# Control_Board_v0_1.net
KiCad netlist of a schematic drawn in EAGLE
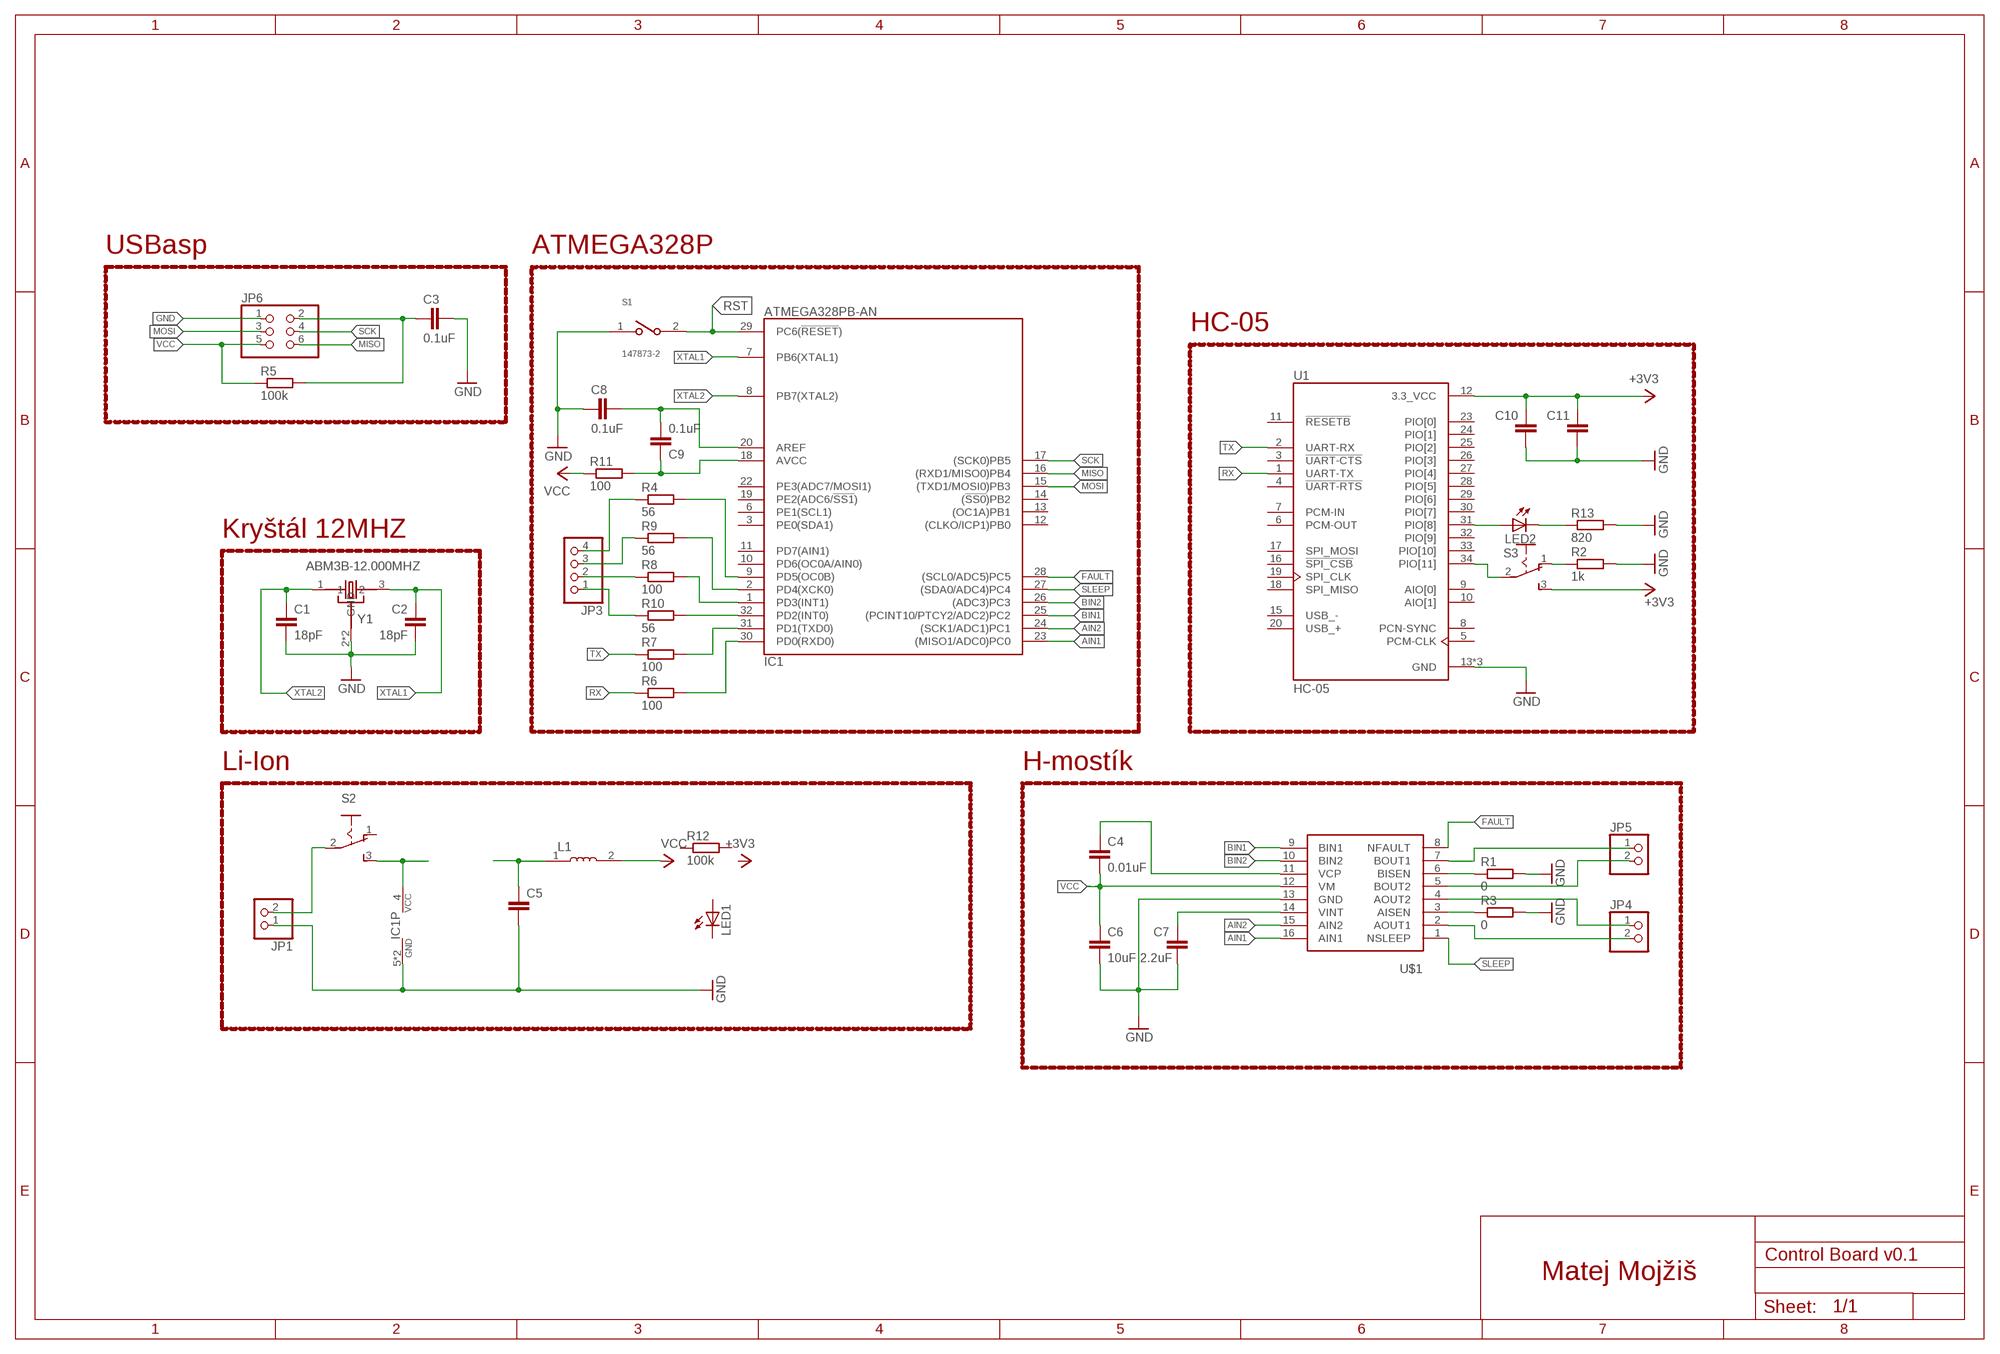
[diagram p0: schematic, sheet 1]

(export (version "E")
  (design (tool "Eeschema 10.0.6"))
  (components
    (comp (ref "C1")
      (value "18pF")
      (footprint "eagle-import:C0805")
      (libsource (lib "eagle-import") (part "C-EUC0805"))
    )
    (comp (ref "C2")
      (value "18pF")
      (footprint "eagle-import:C0805")
      (libsource (lib "eagle-import") (part "C-EUC0805"))
    )
    (comp (ref "C3")
      (value "0.1uF")
      (footprint "eagle-import:C0805")
      (libsource (lib "eagle-import") (part "C-EUC0805"))
    )
    (comp (ref "C4")
      (value "0.01uF")
      (footprint "eagle-import:C0805")
      (libsource (lib "eagle-import") (part "C-EUC0805"))
    )
    (comp (ref "C5")
      (value "C-EUC0805")
      (footprint "eagle-import:C0805")
      (libsource (lib "eagle-import") (part "C-EUC0805"))
    )
    (comp (ref "C6")
      (value "10uF")
      (footprint "eagle-import:C0805")
      (libsource (lib "eagle-import") (part "C-EUC0805"))
    )
    (comp (ref "C7")
      (value "2.2uF")
      (footprint "eagle-import:C0805")
      (libsource (lib "eagle-import") (part "C-EUC0805"))
    )
    (comp (ref "C8")
      (value "0.1uF")
      (footprint "eagle-import:C0805")
      (libsource (lib "eagle-import") (part "C-EUC0805"))
    )
    (comp (ref "C9")
      (value "0.1uF")
      (footprint "eagle-import:C0805")
      (libsource (lib "eagle-import") (part "C-EUC0805"))
    )
    (comp (ref "C10")
      (value "C-EUC0805")
      (footprint "eagle-import:C0805")
      (libsource (lib "eagle-import") (part "C-EUC0805"))
    )
    (comp (ref "C11")
      (value "C-EUC0805")
      (footprint "eagle-import:C0805")
      (libsource (lib "eagle-import") (part "C-EUC0805"))
    )
    (comp (ref "IC1")
      (value "ATMEGA328PB-AN")
      (footprint "eagle-import:QFP32_7X7_0.80")
      (libsource (lib "eagle-import") (part "ATMEGA328PB-AN"))
    )
    (comp (ref "JP1")
      (value "PINHD-1X2/90")
      (footprint "eagle-import:1X02_90")
      (libsource (lib "eagle-import") (part "PINHD-1X2/90"))
    )
    (comp (ref "JP3")
      (value "PINHD-1X4")
      (footprint "eagle-import:1X04")
      (libsource (lib "eagle-import") (part "PINHD-1X4"))
    )
    (comp (ref "JP4")
      (value "PINHD-1X2/90")
      (footprint "eagle-import:1X02_90")
      (libsource (lib "eagle-import") (part "PINHD-1X2/90"))
    )
    (comp (ref "JP5")
      (value "PINHD-1X2/90")
      (footprint "eagle-import:1X02_90")
      (libsource (lib "eagle-import") (part "PINHD-1X2/90"))
    )
    (comp (ref "JP6")
      (value "PINHD-2X3")
      (footprint "eagle-import:2X03")
      (libsource (lib "eagle-import") (part "PINHD-2X3"))
    )
    (comp (ref "L1")
      (value "MLF2012C330KT000")
      (footprint "eagle-import:INDC2012X87N")
      (fields (field (name "MF") "TDK"))
      (libsource (lib "eagle-import") (part "MLF2012C330KT000"))
    )
    (comp (ref "LED1")
      (value "LEDCHIPLED_0805")
      (footprint "eagle-import:CHIPLED_0805")
      (libsource (lib "eagle-import") (part "LEDCHIPLED_0805"))
    )
    (comp (ref "LED2")
      (value "LEDCHIPLED_0805")
      (footprint "eagle-import:CHIPLED_0805")
      (libsource (lib "eagle-import") (part "LEDCHIPLED_0805"))
    )
    (comp (ref "R1")
      (value "0")
      (footprint "eagle-import:R0805")
      (libsource (lib "eagle-import") (part "R-EU_R0805"))
    )
    (comp (ref "R2")
      (value "1k")
      (footprint "eagle-import:R0805")
      (libsource (lib "eagle-import") (part "R-EU_R0805"))
    )
    (comp (ref "R3")
      (value "0")
      (footprint "eagle-import:R0805")
      (libsource (lib "eagle-import") (part "R-EU_R0805"))
    )
    (comp (ref "R4")
      (value "56")
      (footprint "eagle-import:R0805")
      (libsource (lib "eagle-import") (part "R-EU_R0805"))
    )
    (comp (ref "R5")
      (value "100k")
      (footprint "eagle-import:R0805")
      (libsource (lib "eagle-import") (part "R-EU_R0805"))
    )
    (comp (ref "R6")
      (value "100")
      (footprint "eagle-import:R0805")
      (libsource (lib "eagle-import") (part "R-EU_R0805"))
    )
    (comp (ref "R7")
      (value "100")
      (footprint "eagle-import:R0805")
      (libsource (lib "eagle-import") (part "R-EU_R0805"))
    )
    (comp (ref "R8")
      (value "100")
      (footprint "eagle-import:R0805")
      (libsource (lib "eagle-import") (part "R-EU_R0805"))
    )
    (comp (ref "R9")
      (value "56")
      (footprint "eagle-import:R0805")
      (libsource (lib "eagle-import") (part "R-EU_R0805"))
    )
    (comp (ref "R10")
      (value "56")
      (footprint "eagle-import:R0805")
      (libsource (lib "eagle-import") (part "R-EU_R0805"))
    )
    (comp (ref "R11")
      (value "100")
      (footprint "eagle-import:R0805")
      (libsource (lib "eagle-import") (part "R-EU_R0805"))
    )
    (comp (ref "R12")
      (value "100k")
      (footprint "eagle-import:R0805")
      (libsource (lib "eagle-import") (part "R-EU_R0805"))
    )
    (comp (ref "R13")
      (value "820")
      (footprint "eagle-import:R0805")
      (libsource (lib "eagle-import") (part "R-EU_R0805"))
    )
    (comp (ref "S1")
      (value "147873-2")
      (footprint "eagle-import:SW_147873-2")
      (fields (field (name "MF") "TE Connectivity"))
      (libsource (lib "eagle-import") (part "147873-2"))
    )
    (comp (ref "S2")
      (value "255SB")
      (footprint "eagle-import:255SB")
      (libsource (lib "eagle-import") (part "255SB"))
    )
    (comp (ref "S3")
      (value "M251")
      (footprint "eagle-import:M251")
      (libsource (lib "eagle-import") (part "M251"))
    )
    (comp (ref "U$1")
      (value "DVR8833SUPERFICIAL")
      (footprint "eagle-import:PWP16")
      (libsource (lib "eagle-import") (part "DVR8833SUPERFICIAL"))
    )
    (comp (ref "U1")
      (value "HC-05")
      (footprint "eagle-import:XCVR_HC-05")
      (fields (field (name "MF") "Bel Power solution"))
      (libsource (lib "eagle-import") (part "HC-05"))
    )
    (comp (ref "Y1")
      (value "ABM3B-12.000MHZ")
      (footprint "eagle-import:OSCSC500X320X110-4N")
      (fields (field (name "MF") "Abracon") (field (name "MP") "ABM3B-8.000MHZ-B2-T"))
      (libsource (lib "eagle-import") (part "ABM3B-8.000MHZ-B2-T"))
    )
  )
  (nets
    (net (code "1") (name "+3V3") (class "Default")
      (node (ref "C10") (pin "1") (pinfunction "1_1") (pintype "passive"))
      (node (ref "C11") (pin "1") (pinfunction "1_1") (pintype "passive"))
      (node (ref "S3") (pin "3") (pinfunction "S_3") (pintype "passive"))
      (node (ref "U1") (pin "12") (pinfunction "3.3_VCC_12") (pintype "power_in"))
    )
    (net (code "2") (name "AIN1") (class "Default")
      (node (ref "IC1") (pin "23") (pinfunction "(MISO1/ADC0)PC0_23") (pintype "bidirectional"))
      (node (ref "U$1") (pin "16") (pinfunction "AIN1_16") (pintype "bidirectional"))
    )
    (net (code "3") (name "AIN2") (class "Default")
      (node (ref "IC1") (pin "24") (pinfunction "(SCK1/ADC1)PC1_24") (pintype "bidirectional"))
      (node (ref "U$1") (pin "15") (pinfunction "AIN2_15") (pintype "bidirectional"))
    )
    (net (code "4") (name "BIN1") (class "Default")
      (node (ref "IC1") (pin "25") (pinfunction "(PCINT10/PTCY2/ADC2)PC2_25") (pintype "bidirectional"))
      (node (ref "U$1") (pin "9") (pinfunction "BIN1_9") (pintype "bidirectional"))
    )
    (net (code "5") (name "BIN2") (class "Default")
      (node (ref "IC1") (pin "26") (pinfunction "(ADC3)PC3_26") (pintype "bidirectional"))
      (node (ref "U$1") (pin "10") (pinfunction "BIN2_10") (pintype "bidirectional"))
    )
    (net (code "6") (name "FAULT") (class "Default")
      (node (ref "IC1") (pin "28") (pinfunction "(SCL0/ADC5)PC5_28") (pintype "bidirectional"))
      (node (ref "U$1") (pin "8") (pinfunction "NFAULT_8") (pintype "bidirectional"))
    )
    (net (code "7") (name "GND") (class "Default")
      (node (ref "C1") (pin "2") (pinfunction "2_2") (pintype "passive"))
      (node (ref "C10") (pin "2") (pinfunction "2_2") (pintype "passive"))
      (node (ref "C11") (pin "2") (pinfunction "2_2") (pintype "passive"))
      (node (ref "C2") (pin "2") (pinfunction "2_2") (pintype "passive"))
      (node (ref "C3") (pin "1") (pinfunction "1_1") (pintype "passive"))
      (node (ref "C5") (pin "2") (pinfunction "2_2") (pintype "passive"))
      (node (ref "C6") (pin "2") (pinfunction "2_2") (pintype "passive"))
      (node (ref "C7") (pin "2") (pinfunction "2_2") (pintype "passive"))
      (node (ref "C8") (pin "2") (pinfunction "2_2") (pintype "passive"))
      (node (ref "IC1") (pin "21") (pinfunction "GND_21") (pintype "power_in"))
      (node (ref "IC1") (pin "5") (pinfunction "GND_5") (pintype "power_in"))
      (node (ref "JP1") (pin "1") (pinfunction "1_1") (pintype "passive"))
      (node (ref "JP6") (pin "1") (pinfunction "1_1") (pintype "passive"))
      (node (ref "R1") (pin "2") (pinfunction "2_2") (pintype "passive"))
      (node (ref "R13") (pin "2") (pinfunction "2_2") (pintype "passive"))
      (node (ref "R2") (pin "2") (pinfunction "2_2") (pintype "passive"))
      (node (ref "R3") (pin "2") (pinfunction "2_2") (pintype "passive"))
      (node (ref "S1") (pin "1") (pinfunction "1_1") (pintype "passive"))
      (node (ref "U$1") (pin "13") (pinfunction "GND_13") (pintype "bidirectional"))
      (node (ref "U1") (pin "13") (pinfunction "GND_13") (pintype "power_in"))
      (node (ref "U1") (pin "21") (pinfunction "GND_21") (pintype "power_in"))
      (node (ref "U1") (pin "22") (pinfunction "GND_22") (pintype "power_in"))
      (node (ref "Y1") (pin "2") (pinfunction "GND_2") (pintype "passive"))
      (node (ref "Y1") (pin "4") (pinfunction "GND_4") (pintype "passive"))
    )
    (net (code "8") (name "MISO") (class "Default")
      (node (ref "IC1") (pin "16") (pinfunction "(RXD1/MISO0)PB4_16") (pintype "bidirectional"))
      (node (ref "JP6") (pin "6") (pinfunction "6_6") (pintype "passive"))
    )
    (net (code "9") (name "MOSI") (class "Default")
      (node (ref "IC1") (pin "15") (pinfunction "(TXD1/MOSI0)PB3_15") (pintype "bidirectional"))
      (node (ref "JP6") (pin "3") (pinfunction "3_3") (pintype "passive"))
    )
    (net (code "10") (name "Net-(C5-Pad1)") (class "Default")
      (node (ref "C5") (pin "1") (pinfunction "1_1") (pintype "passive"))
      (node (ref "L1") (pin "1") (pinfunction "1_1") (pintype "passive"))
    )
    (net (code "11") (name "Net-(IC1A-AREF)") (class "Default")
      (node (ref "C8") (pin "1") (pinfunction "1_1") (pintype "passive"))
      (node (ref "C9") (pin "2") (pinfunction "2_2") (pintype "passive"))
      (node (ref "IC1") (pin "20") (pinfunction "AREF_20") (pintype "passive"))
    )
    (net (code "12") (name "Net-(IC1A-AVCC)") (class "Default")
      (node (ref "C9") (pin "1") (pinfunction "1_1") (pintype "passive"))
      (node (ref "IC1") (pin "18") (pinfunction "AVCC_18") (pintype "power_in"))
      (node (ref "R11") (pin "2") (pinfunction "2_2") (pintype "passive"))
    )
    (net (code "13") (name "Net-(IC1A-PD0(RXD0))") (class "Default")
      (node (ref "IC1") (pin "30") (pinfunction "PD0(RXD0)_30") (pintype "bidirectional"))
      (node (ref "R6") (pin "2") (pinfunction "2_2") (pintype "passive"))
    )
    (net (code "14") (name "Net-(IC1A-PD1(TXD0))") (class "Default")
      (node (ref "IC1") (pin "31") (pinfunction "PD1(TXD0)_31") (pintype "bidirectional"))
      (node (ref "R7") (pin "2") (pinfunction "2_2") (pintype "passive"))
    )
    (net (code "15") (name "Net-(IC1A-PD2(INT0))") (class "Default")
      (node (ref "IC1") (pin "32") (pinfunction "PD2(INT0)_32") (pintype "bidirectional"))
      (node (ref "R10") (pin "2") (pinfunction "2_2") (pintype "passive"))
    )
    (net (code "16") (name "Net-(IC1A-PD3(INT1))") (class "Default")
      (node (ref "IC1") (pin "1") (pinfunction "PD3(INT1)_1") (pintype "bidirectional"))
      (node (ref "R8") (pin "2") (pinfunction "2_2") (pintype "passive"))
    )
    (net (code "17") (name "Net-(IC1A-PD4(XCK0))") (class "Default")
      (node (ref "IC1") (pin "2") (pinfunction "PD4(XCK0)_2") (pintype "bidirectional"))
      (node (ref "R9") (pin "2") (pinfunction "2_2") (pintype "passive"))
    )
    (net (code "18") (name "Net-(IC1A-PD5(OC0B))") (class "Default")
      (node (ref "IC1") (pin "9") (pinfunction "PD5(OC0B)_9") (pintype "bidirectional"))
      (node (ref "R4") (pin "2") (pinfunction "2_2") (pintype "passive"))
    )
    (net (code "19") (name "Net-(IC1B-VCC)") (class "Default")
      (node (ref "IC1") (pin "4") (pinfunction "VCC_4") (pintype "power_in"))
      (node (ref "S2") (pin "3") (pinfunction "S_3") (pintype "passive"))
    )
    (net (code "20") (name "Net-(JP3-Pad1)") (class "Default")
      (node (ref "JP3") (pin "1") (pinfunction "1_1") (pintype "passive"))
      (node (ref "R10") (pin "1") (pinfunction "1_1") (pintype "passive"))
    )
    (net (code "21") (name "Net-(JP3-Pad2)") (class "Default")
      (node (ref "JP3") (pin "2") (pinfunction "2_2") (pintype "passive"))
      (node (ref "R8") (pin "1") (pinfunction "1_1") (pintype "passive"))
    )
    (net (code "22") (name "Net-(JP3-Pad3)") (class "Default")
      (node (ref "JP3") (pin "3") (pinfunction "3_3") (pintype "passive"))
      (node (ref "R9") (pin "1") (pinfunction "1_1") (pintype "passive"))
    )
    (net (code "23") (name "Net-(JP3-Pad4)") (class "Default")
      (node (ref "JP3") (pin "4") (pinfunction "4_4") (pintype "passive"))
      (node (ref "R4") (pin "1") (pinfunction "1_1") (pintype "passive"))
    )
    (net (code "24") (name "Net-(LED2-PadC)") (class "Default")
      (node (ref "LED2") (pin "C") (pinfunction "C_C") (pintype "passive"))
      (node (ref "R13") (pin "1") (pinfunction "1_1") (pintype "passive"))
    )
    (net (code "25") (name "Net-(S2-P)") (class "Default")
      (node (ref "JP1") (pin "2") (pinfunction "2_2") (pintype "passive"))
      (node (ref "S2") (pin "2") (pinfunction "P_2") (pintype "passive"))
    )
    (net (code "26") (name "Net-(S3-O)") (class "Default")
      (node (ref "R2") (pin "1") (pinfunction "1_1") (pintype "passive"))
      (node (ref "S3") (pin "1") (pinfunction "O_1") (pintype "passive"))
    )
    (net (code "27") (name "Net-(S3-P)") (class "Default")
      (node (ref "S3") (pin "2") (pinfunction "P_2") (pintype "passive"))
      (node (ref "U1") (pin "34") (pinfunction "PIO[11]_34") (pintype "bidirectional"))
    )
    (net (code "28") (name "Net-(U$1-AISEN)") (class "Default")
      (node (ref "R3") (pin "1") (pinfunction "1_1") (pintype "passive"))
      (node (ref "U$1") (pin "3") (pinfunction "AISEN_3") (pintype "bidirectional"))
    )
    (net (code "29") (name "Net-(U$1-AOUT1)") (class "Default")
      (node (ref "JP4") (pin "2") (pinfunction "2_2") (pintype "passive"))
      (node (ref "U$1") (pin "2") (pinfunction "AOUT1_2") (pintype "bidirectional"))
    )
    (net (code "30") (name "Net-(U$1-AOUT2)") (class "Default")
      (node (ref "JP4") (pin "1") (pinfunction "1_1") (pintype "passive"))
      (node (ref "U$1") (pin "4") (pinfunction "AOUT2_4") (pintype "bidirectional"))
    )
    (net (code "31") (name "Net-(U$1-BISEN)") (class "Default")
      (node (ref "R1") (pin "1") (pinfunction "1_1") (pintype "passive"))
      (node (ref "U$1") (pin "6") (pinfunction "BISEN_6") (pintype "bidirectional"))
    )
    (net (code "32") (name "Net-(U$1-BOUT1)") (class "Default")
      (node (ref "JP5") (pin "1") (pinfunction "1_1") (pintype "passive"))
      (node (ref "U$1") (pin "7") (pinfunction "BOUT1_7") (pintype "bidirectional"))
    )
    (net (code "33") (name "Net-(U$1-BOUT2)") (class "Default")
      (node (ref "JP5") (pin "2") (pinfunction "2_2") (pintype "passive"))
      (node (ref "U$1") (pin "5") (pinfunction "BOUT2_5") (pintype "bidirectional"))
    )
    (net (code "34") (name "Net-(U$1-VCP)") (class "Default")
      (node (ref "C4") (pin "1") (pinfunction "1_1") (pintype "passive"))
      (node (ref "U$1") (pin "11") (pinfunction "VCP_11") (pintype "bidirectional"))
    )
    (net (code "35") (name "Net-(U$1-VINT)") (class "Default")
      (node (ref "C7") (pin "1") (pinfunction "1_1") (pintype "passive"))
      (node (ref "U$1") (pin "14") (pinfunction "VINT_14") (pintype "bidirectional"))
    )
    (net (code "36") (name "Net-(U1-PIO[8])") (class "Default")
      (node (ref "LED2") (pin "A") (pinfunction "A_A") (pintype "passive"))
      (node (ref "U1") (pin "31") (pinfunction "PIO[8]_31") (pintype "bidirectional"))
    )
    (net (code "37") (name "RST") (class "Default")
      (node (ref "C3") (pin "2") (pinfunction "2_2") (pintype "passive"))
      (node (ref "IC1") (pin "29") (pinfunction "PC6(~{RESET})_29") (pintype "bidirectional"))
      (node (ref "JP6") (pin "2") (pinfunction "2_2") (pintype "passive"))
      (node (ref "R5") (pin "2") (pinfunction "2_2") (pintype "passive"))
      (node (ref "S1") (pin "2") (pinfunction "2_2") (pintype "passive"))
    )
    (net (code "38") (name "RX") (class "Default")
      (node (ref "R6") (pin "1") (pinfunction "1_1") (pintype "passive"))
      (node (ref "U1") (pin "1") (pinfunction "UART-TX_1") (pintype "output"))
    )
    (net (code "39") (name "SCK") (class "Default")
      (node (ref "IC1") (pin "17") (pinfunction "(SCK0)PB5_17") (pintype "bidirectional"))
      (node (ref "JP6") (pin "4") (pinfunction "4_4") (pintype "passive"))
    )
    (net (code "40") (name "SLEEP") (class "Default")
      (node (ref "IC1") (pin "27") (pinfunction "(SDA0/ADC4)PC4_27") (pintype "bidirectional"))
      (node (ref "U$1") (pin "1") (pinfunction "NSLEEP_1") (pintype "bidirectional"))
    )
    (net (code "41") (name "TX") (class "Default")
      (node (ref "R7") (pin "1") (pinfunction "1_1") (pintype "passive"))
      (node (ref "U1") (pin "2") (pinfunction "UART-RX_2") (pintype "input"))
    )
    (net (code "42") (name "VCC") (class "Default")
      (node (ref "C4") (pin "2") (pinfunction "2_2") (pintype "passive"))
      (node (ref "C6") (pin "1") (pinfunction "1_1") (pintype "passive"))
      (node (ref "JP6") (pin "5") (pinfunction "5_5") (pintype "passive"))
      (node (ref "L1") (pin "2") (pinfunction "2_2") (pintype "passive"))
      (node (ref "R11") (pin "1") (pinfunction "1_1") (pintype "passive"))
      (node (ref "R5") (pin "1") (pinfunction "1_1") (pintype "passive"))
      (node (ref "U$1") (pin "12") (pinfunction "VM_12") (pintype "bidirectional"))
    )
    (net (code "43") (name "XTAL1") (class "Default")
      (node (ref "C2") (pin "1") (pinfunction "1_1") (pintype "passive"))
      (node (ref "IC1") (pin "7") (pinfunction "PB6(XTAL1)_7") (pintype "bidirectional"))
      (node (ref "Y1") (pin "3") (pinfunction "2_3") (pintype "passive"))
    )
    (net (code "44") (name "XTAL2") (class "Default")
      (node (ref "C1") (pin "1") (pinfunction "1_1") (pintype "passive"))
      (node (ref "IC1") (pin "8") (pinfunction "PB7(XTAL2)_8") (pintype "bidirectional"))
      (node (ref "Y1") (pin "1") (pinfunction "1_1") (pintype "passive"))
    )
    (net (code "45") (name "unconnected-(IC1A-(CLKO{slash}ICP1)PB0-Pad12)") (class "Default")
      (node (ref "IC1") (pin "12") (pinfunction "(CLKO/ICP1)PB0_12") (pintype "bidirectional"))
    )
    (net (code "46") (name "unconnected-(IC1A-(OC1A)PB1-Pad13)") (class "Default")
      (node (ref "IC1") (pin "13") (pinfunction "(OC1A)PB1_13") (pintype "bidirectional"))
    )
    (net (code "47") (name "unconnected-(IC1A-(~{SS0})PB2-Pad14)") (class "Default")
      (node (ref "IC1") (pin "14") (pinfunction "(~{SS0})PB2_14") (pintype "bidirectional"))
    )
    (net (code "48") (name "unconnected-(IC1A-PD6(OC0A{slash}AIN0)-Pad10)") (class "Default")
      (node (ref "IC1") (pin "10") (pinfunction "PD6(OC0A/AIN0)_10") (pintype "bidirectional"))
    )
    (net (code "49") (name "unconnected-(IC1A-PD7(AIN1)-Pad11)") (class "Default")
      (node (ref "IC1") (pin "11") (pinfunction "PD7(AIN1)_11") (pintype "bidirectional"))
    )
    (net (code "50") (name "unconnected-(IC1A-PE0(SDA1)-Pad3)") (class "Default")
      (node (ref "IC1") (pin "3") (pinfunction "PE0(SDA1)_3") (pintype "bidirectional"))
    )
    (net (code "51") (name "unconnected-(IC1A-PE1(SCL1)-Pad6)") (class "Default")
      (node (ref "IC1") (pin "6") (pinfunction "PE1(SCL1)_6") (pintype "bidirectional"))
    )
    (net (code "52") (name "unconnected-(IC1A-PE2(ADC6{slash}~{SS1})-Pad19)") (class "Default")
      (node (ref "IC1") (pin "19") (pinfunction "PE2(ADC6/~{SS1})_19") (pintype "bidirectional"))
    )
    (net (code "53") (name "unconnected-(IC1A-PE3(ADC7{slash}MOSI1)-Pad22)") (class "Default")
      (node (ref "IC1") (pin "22") (pinfunction "PE3(ADC7/MOSI1)_22") (pintype "bidirectional"))
    )
    (net (code "54") (name "unconnected-(LED1-PadA)") (class "Default")
      (node (ref "LED1") (pin "A") (pinfunction "A_A") (pintype "passive"))
    )
    (net (code "55") (name "unconnected-(LED1-PadC)") (class "Default")
      (node (ref "LED1") (pin "C") (pinfunction "C_C") (pintype "passive"))
    )
    (net (code "56") (name "unconnected-(R12-Pad1)") (class "Default")
      (node (ref "R12") (pin "1") (pinfunction "1_1") (pintype "passive"))
    )
    (net (code "57") (name "unconnected-(R12-Pad2)") (class "Default")
      (node (ref "R12") (pin "2") (pinfunction "2_2") (pintype "passive"))
    )
    (net (code "58") (name "unconnected-(S2-O-Pad1)") (class "Default")
      (node (ref "S2") (pin "1") (pinfunction "O_1") (pintype "passive"))
    )
    (net (code "59") (name "unconnected-(U1-AIO[0]-Pad9)") (class "Default")
      (node (ref "U1") (pin "9") (pinfunction "AIO[0]_9") (pintype "bidirectional"))
    )
    (net (code "60") (name "unconnected-(U1-AIO[1]-Pad10)") (class "Default")
      (node (ref "U1") (pin "10") (pinfunction "AIO[1]_10") (pintype "bidirectional"))
    )
    (net (code "61") (name "unconnected-(U1-PCM-CLK-Pad5)") (class "Default")
      (node (ref "U1") (pin "5") (pinfunction "PCM-CLK_5") (pintype "bidirectional"))
    )
    (net (code "62") (name "unconnected-(U1-PCM-IN-Pad7)") (class "Default")
      (node (ref "U1") (pin "7") (pinfunction "PCM-IN_7") (pintype "input"))
    )
    (net (code "63") (name "unconnected-(U1-PCM-OUT-Pad6)") (class "Default")
      (node (ref "U1") (pin "6") (pinfunction "PCM-OUT_6") (pintype "output"))
    )
    (net (code "64") (name "unconnected-(U1-PCN-SYNC-Pad8)") (class "Default")
      (node (ref "U1") (pin "8") (pinfunction "PCN-SYNC_8") (pintype "bidirectional"))
    )
    (net (code "65") (name "unconnected-(U1-PIO[0]-Pad23)") (class "Default")
      (node (ref "U1") (pin "23") (pinfunction "PIO[0]_23") (pintype "bidirectional"))
    )
    (net (code "66") (name "unconnected-(U1-PIO[1]-Pad24)") (class "Default")
      (node (ref "U1") (pin "24") (pinfunction "PIO[1]_24") (pintype "bidirectional"))
    )
    (net (code "67") (name "unconnected-(U1-PIO[2]-Pad25)") (class "Default")
      (node (ref "U1") (pin "25") (pinfunction "PIO[2]_25") (pintype "bidirectional"))
    )
    (net (code "68") (name "unconnected-(U1-PIO[3]-Pad26)") (class "Default")
      (node (ref "U1") (pin "26") (pinfunction "PIO[3]_26") (pintype "bidirectional"))
    )
    (net (code "69") (name "unconnected-(U1-PIO[4]-Pad27)") (class "Default")
      (node (ref "U1") (pin "27") (pinfunction "PIO[4]_27") (pintype "bidirectional"))
    )
    (net (code "70") (name "unconnected-(U1-PIO[5]-Pad28)") (class "Default")
      (node (ref "U1") (pin "28") (pinfunction "PIO[5]_28") (pintype "bidirectional"))
    )
    (net (code "71") (name "unconnected-(U1-PIO[6]-Pad29)") (class "Default")
      (node (ref "U1") (pin "29") (pinfunction "PIO[6]_29") (pintype "bidirectional"))
    )
    (net (code "72") (name "unconnected-(U1-PIO[7]-Pad30)") (class "Default")
      (node (ref "U1") (pin "30") (pinfunction "PIO[7]_30") (pintype "bidirectional"))
    )
    (net (code "73") (name "unconnected-(U1-PIO[9]-Pad32)") (class "Default")
      (node (ref "U1") (pin "32") (pinfunction "PIO[9]_32") (pintype "bidirectional"))
    )
    (net (code "74") (name "unconnected-(U1-PIO[10]-Pad33)") (class "Default")
      (node (ref "U1") (pin "33") (pinfunction "PIO[10]_33") (pintype "bidirectional"))
    )
    (net (code "75") (name "unconnected-(U1-SPI_CLK-Pad19)") (class "Default")
      (node (ref "U1") (pin "19") (pinfunction "SPI_CLK_19") (pintype "input"))
    )
    (net (code "76") (name "unconnected-(U1-SPI_MISO-Pad18)") (class "Default")
      (node (ref "U1") (pin "18") (pinfunction "SPI_MISO_18") (pintype "output"))
    )
    (net (code "77") (name "unconnected-(U1-SPI_MOSI-Pad17)") (class "Default")
      (node (ref "U1") (pin "17") (pinfunction "SPI_MOSI_17") (pintype "input"))
    )
    (net (code "78") (name "unconnected-(U1-USB_+-Pad20)") (class "Default")
      (node (ref "U1") (pin "20") (pinfunction "USB_+_20") (pintype "bidirectional"))
    )
    (net (code "79") (name "unconnected-(U1-USB_--Pad15)") (class "Default")
      (node (ref "U1") (pin "15") (pinfunction "USB_-_15") (pintype "bidirectional"))
    )
    (net (code "80") (name "unconnected-(U1-~{RESETB}-Pad11)") (class "Default")
      (node (ref "U1") (pin "11") (pinfunction "~{RESETB}_11") (pintype "input"))
    )
    (net (code "81") (name "unconnected-(U1-~{SPI_CSB}-Pad16)") (class "Default")
      (node (ref "U1") (pin "16") (pinfunction "~{SPI_CSB}_16") (pintype "input"))
    )
    (net (code "82") (name "unconnected-(U1-~{UART-CTS}-Pad3)") (class "Default")
      (node (ref "U1") (pin "3") (pinfunction "~{UART-CTS}_3") (pintype "input"))
    )
    (net (code "83") (name "unconnected-(U1-~{UART-RTS}-Pad4)") (class "Default")
      (node (ref "U1") (pin "4") (pinfunction "~{UART-RTS}_4") (pintype "output"))
    )
  )
)
